# test_o1.net
KiCad netlist of a schematic drawn in EAGLE
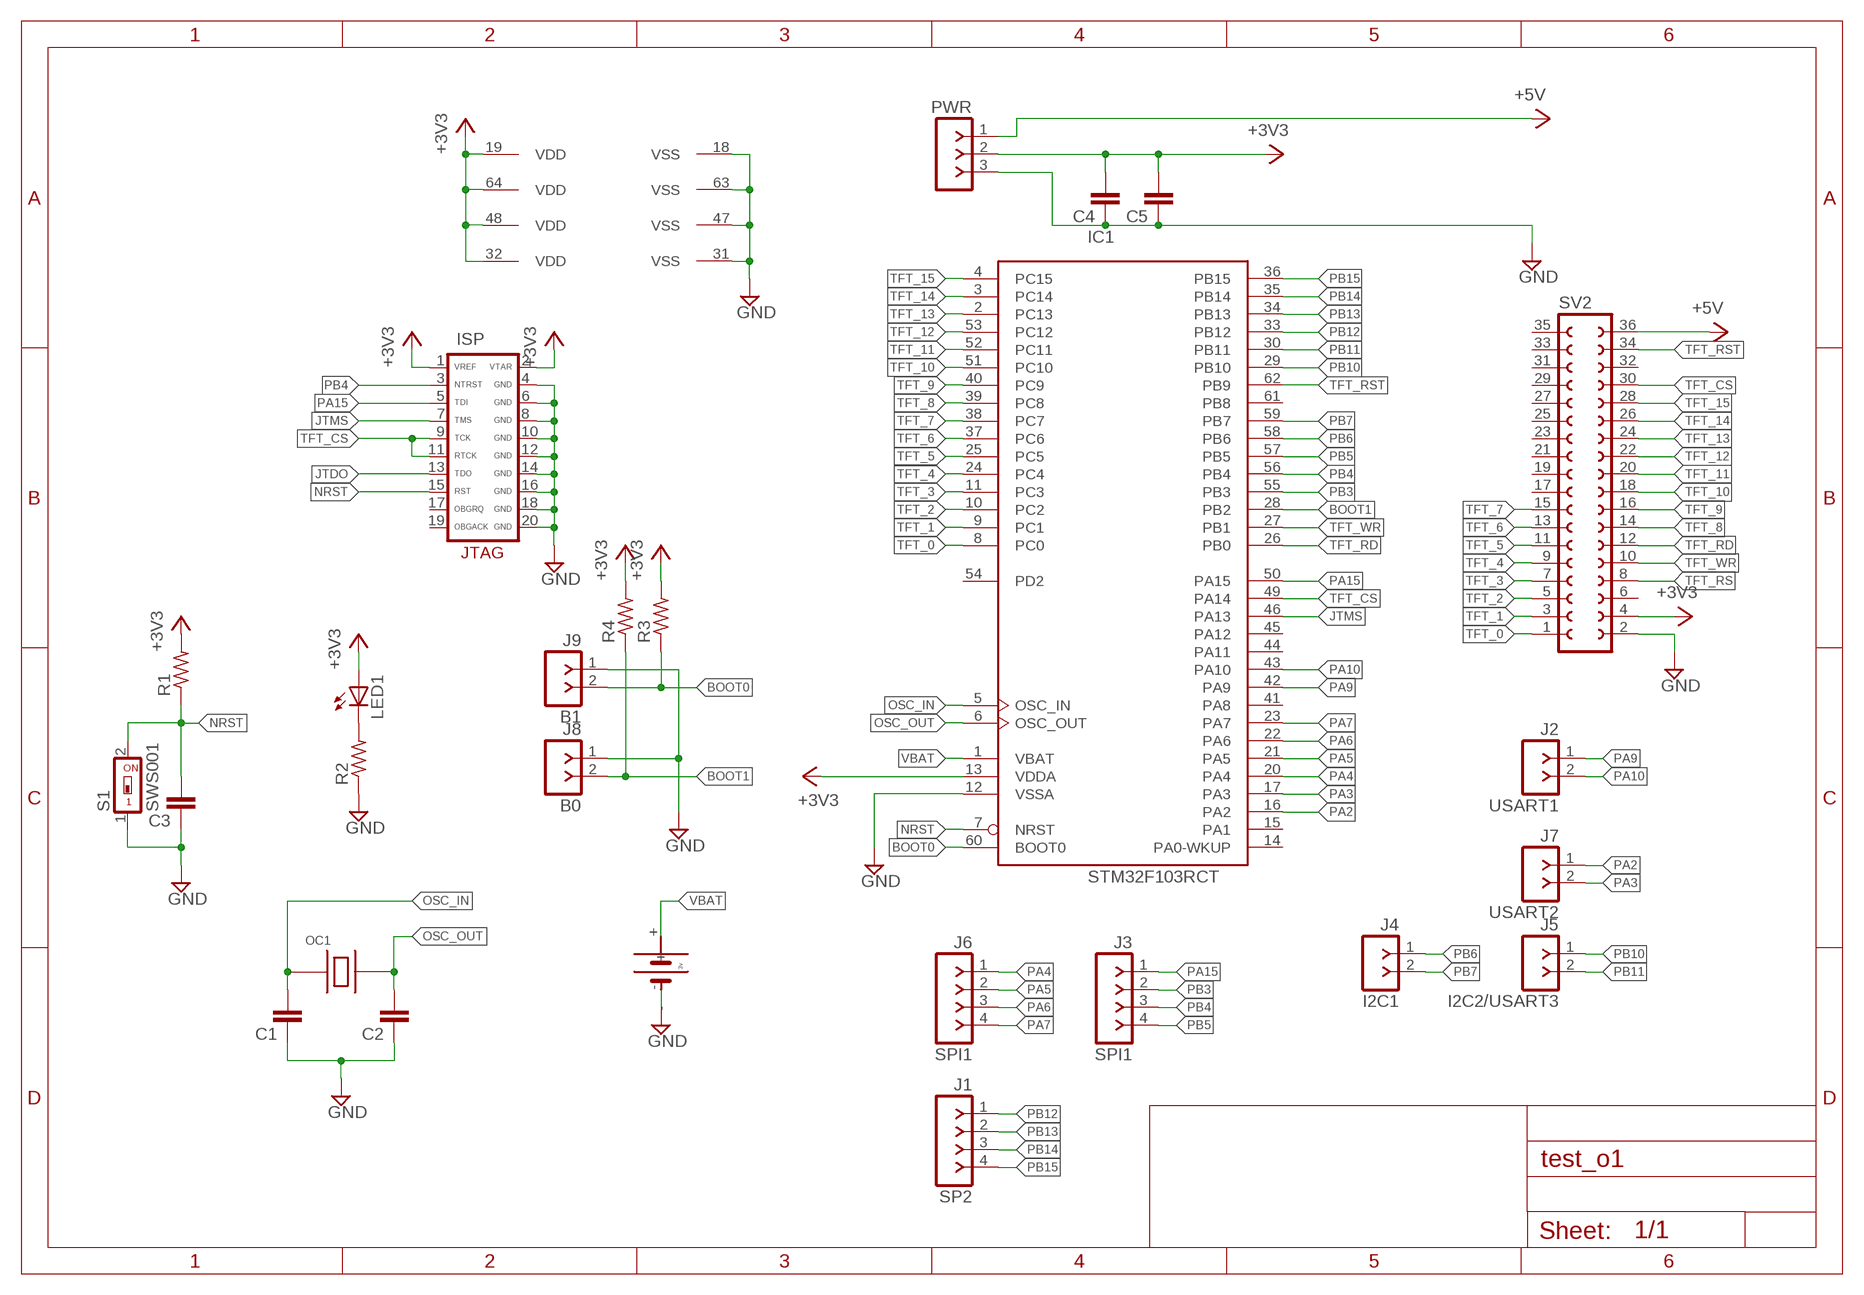
[diagram p0: schematic, sheet 1]

(export (version "E")
  (design (tool "Eeschema 10.0.6"))
  (components
    (comp (ref "C1")
      (value "C-EUC1206")
      (footprint "eagle-import:C1206")
      (libsource (lib "eagle-import") (part "C-EUC1206"))
    )
    (comp (ref "C2")
      (value "C-EUC1206")
      (footprint "eagle-import:C1206")
      (libsource (lib "eagle-import") (part "C-EUC1206"))
    )
    (comp (ref "C3")
      (value "C-EUC1206")
      (footprint "eagle-import:C1206")
      (libsource (lib "eagle-import") (part "C-EUC1206"))
    )
    (comp (ref "C4")
      (value "C-EUC1206")
      (footprint "eagle-import:C1206")
      (libsource (lib "eagle-import") (part "C-EUC1206"))
    )
    (comp (ref "C5")
      (value "C-EUC1206")
      (footprint "eagle-import:C1206")
      (libsource (lib "eagle-import") (part "C-EUC1206"))
    )
    (comp (ref "IC1")
      (value "STM32F103RCT")
      (footprint "eagle-import:LQFP64")
      (libsource (lib "eagle-import") (part "STM32F103RTC"))
    )
    (comp (ref "ISP")
      (value "JTAG")
      (footprint "eagle-import:PAK100_2500-20")
      (libsource (lib "eagle-import") (part "JTAG-ARM-PAK100/2500-20"))
    )
    (comp (ref "J1")
      (value "SP2")
      (footprint "eagle-import:SIP-100-04-40")
      (libsource (lib "eagle-import") (part "F-1X04-SIP-100-40"))
    )
    (comp (ref "J2")
      (value "USART1")
      (footprint "eagle-import:SIP-100-02-40")
      (libsource (lib "eagle-import") (part "F-1X02-SIP-100-40"))
    )
    (comp (ref "J3")
      (value "SPI1")
      (footprint "eagle-import:SIP-100-04-40")
      (libsource (lib "eagle-import") (part "F-1X04-SIP-100-40"))
    )
    (comp (ref "J4")
      (value "I2C1")
      (footprint "eagle-import:SIP-100-02-40")
      (libsource (lib "eagle-import") (part "F-1X02-SIP-100-40"))
    )
    (comp (ref "J5")
      (value "I2C2/USART3")
      (footprint "eagle-import:SIP-100-02-40")
      (libsource (lib "eagle-import") (part "F-1X02-SIP-100-40"))
    )
    (comp (ref "J6")
      (value "SPI1")
      (footprint "eagle-import:SIP-100-04-40")
      (libsource (lib "eagle-import") (part "F-1X04-SIP-100-40"))
    )
    (comp (ref "J7")
      (value "USART2")
      (footprint "eagle-import:SIP-100-02-40")
      (libsource (lib "eagle-import") (part "F-1X02-SIP-100-40"))
    )
    (comp (ref "J8")
      (value "B0")
      (footprint "eagle-import:SIP-100-02-40")
      (libsource (lib "eagle-import") (part "F-1X02-SIP-100-40"))
    )
    (comp (ref "J9")
      (value "B1")
      (footprint "eagle-import:SIP-100-02-40")
      (libsource (lib "eagle-import") (part "F-1X02-SIP-100-40"))
    )
    (comp (ref "LED1")
      (value "LEDSML1206")
      (footprint "eagle-import:SML1206")
      (libsource (lib "eagle-import") (part "LEDSML1206"))
    )
    (comp (ref "OC1")
      (value "SMAQ-7050B")
      (footprint "eagle-import:IQG7050B")
      (libsource (lib "eagle-import") (part "SMAQ-7050B"))
    )
    (comp (ref "PWR")
      (value "F-1X03-SIP-100-40")
      (footprint "eagle-import:SIP-100-03-40")
      (libsource (lib "eagle-import") (part "F-1X03-SIP-100-40"))
    )
    (comp (ref "R1")
      (value "R-US_R1206")
      (footprint "eagle-import:R1206")
      (libsource (lib "eagle-import") (part "R-US_R1206"))
    )
    (comp (ref "R2")
      (value "R-US_R1206")
      (footprint "eagle-import:R1206")
      (libsource (lib "eagle-import") (part "R-US_R1206"))
    )
    (comp (ref "R3")
      (value "R-US_R1206")
      (footprint "eagle-import:R1206")
      (libsource (lib "eagle-import") (part "R-US_R1206"))
    )
    (comp (ref "R4")
      (value "R-US_R1206")
      (footprint "eagle-import:R1206")
      (libsource (lib "eagle-import") (part "R-US_R1206"))
    )
    (comp (ref "S1")
      (value "SWS001")
      (footprint "eagle-import:SMS-001")
      (libsource (lib "eagle-import") (part "SWS001"))
    )
    (comp (ref "SV2")
      (value "FE18-2")
      (footprint "eagle-import:FE18-2")
      (libsource (lib "eagle-import") (part "FE18-2"))
    )
    (comp (ref "U$2")
      (value "1220BATTERY_SF")
      (footprint "eagle-import:1220BATTERY")
      (libsource (lib "eagle-import") (part "1220BATTERY_SF"))
    )
  )
  (nets
    (net (code "1") (name "+3V3") (class "Default")
      (node (ref "C4") (pin "2") (pinfunction "2_2") (pintype "passive"))
      (node (ref "C5") (pin "2") (pinfunction "2_2") (pintype "passive"))
      (node (ref "IC1") (pin "13") (pinfunction "VDDA_13") (pintype "power_in"))
      (node (ref "IC1") (pin "19") (pinfunction "VDD_19") (pintype "power_in"))
      (node (ref "IC1") (pin "32") (pinfunction "VDD_32") (pintype "power_in"))
      (node (ref "IC1") (pin "48") (pinfunction "VDD_48") (pintype "power_in"))
      (node (ref "IC1") (pin "64") (pinfunction "VDD_64") (pintype "power_in"))
      (node (ref "ISP") (pin "1") (pinfunction "VREF_1") (pintype "passive"))
      (node (ref "ISP") (pin "2") (pinfunction "VTAR_2") (pintype "passive"))
      (node (ref "LED1") (pin "A") (pinfunction "A_A") (pintype "passive"))
      (node (ref "PWR") (pin "2") (pinfunction "2_2") (pintype "passive"))
      (node (ref "R1") (pin "2") (pinfunction "2_2") (pintype "passive"))
      (node (ref "R3") (pin "2") (pinfunction "2_2") (pintype "passive"))
      (node (ref "R4") (pin "2") (pinfunction "2_2") (pintype "passive"))
      (node (ref "SV2") (pin "4") (pinfunction "4_4") (pintype "passive"))
    )
    (net (code "2") (name "+5V") (class "Default")
      (node (ref "PWR") (pin "1") (pinfunction "1_1") (pintype "passive"))
      (node (ref "SV2") (pin "36") (pinfunction "36_36") (pintype "passive"))
    )
    (net (code "3") (name "BOOT0") (class "Default")
      (node (ref "IC1") (pin "60") (pinfunction "BOOT0_60") (pintype "input"))
      (node (ref "J9") (pin "2") (pinfunction "2_2") (pintype "passive"))
      (node (ref "R3") (pin "1") (pinfunction "1_1") (pintype "passive"))
    )
    (net (code "4") (name "BOOT1") (class "Default")
      (node (ref "IC1") (pin "28") (pinfunction "PB2_28") (pintype "bidirectional"))
      (node (ref "J8") (pin "2") (pinfunction "2_2") (pintype "passive"))
      (node (ref "R4") (pin "1") (pinfunction "1_1") (pintype "passive"))
    )
    (net (code "5") (name "GND") (class "Default")
      (node (ref "C1") (pin "1") (pinfunction "1_1") (pintype "passive"))
      (node (ref "C2") (pin "1") (pinfunction "1_1") (pintype "passive"))
      (node (ref "C3") (pin "1") (pinfunction "1_1") (pintype "passive"))
      (node (ref "C4") (pin "1") (pinfunction "1_1") (pintype "passive"))
      (node (ref "C5") (pin "1") (pinfunction "1_1") (pintype "passive"))
      (node (ref "IC1") (pin "12") (pinfunction "VSSA_12") (pintype "power_in"))
      (node (ref "IC1") (pin "18") (pinfunction "VSS_18") (pintype "power_in"))
      (node (ref "IC1") (pin "31") (pinfunction "VSS_31") (pintype "power_in"))
      (node (ref "IC1") (pin "47") (pinfunction "VSS_47") (pintype "power_in"))
      (node (ref "IC1") (pin "63") (pinfunction "VSS_63") (pintype "power_in"))
      (node (ref "ISP") (pin "10") (pinfunction "GND_10") (pintype "passive"))
      (node (ref "ISP") (pin "12") (pinfunction "GND_12") (pintype "passive"))
      (node (ref "ISP") (pin "14") (pinfunction "GND_14") (pintype "passive"))
      (node (ref "ISP") (pin "16") (pinfunction "GND_16") (pintype "passive"))
      (node (ref "ISP") (pin "18") (pinfunction "GND_18") (pintype "passive"))
      (node (ref "ISP") (pin "20") (pinfunction "GND_20") (pintype "passive"))
      (node (ref "ISP") (pin "4") (pinfunction "GND_4") (pintype "passive"))
      (node (ref "ISP") (pin "6") (pinfunction "GND_6") (pintype "passive"))
      (node (ref "ISP") (pin "8") (pinfunction "GND_8") (pintype "passive"))
      (node (ref "J8") (pin "1") (pinfunction "1_1") (pintype "passive"))
      (node (ref "J9") (pin "1") (pinfunction "1_1") (pintype "passive"))
      (node (ref "PWR") (pin "3") (pinfunction "3_3") (pintype "passive"))
      (node (ref "R2") (pin "1") (pinfunction "1_1") (pintype "passive"))
      (node (ref "S1") (pin "1") (pinfunction "1_1") (pintype "passive"))
      (node (ref "SV2") (pin "2") (pinfunction "2_2") (pintype "passive"))
      (node (ref "U$2") (pin "-") (pinfunction "-_-") (pintype "bidirectional"))
    )
    (net (code "6") (name "JTDO") (class "Default")
      (node (ref "ISP") (pin "13") (pinfunction "TDO_13") (pintype "passive"))
    )
    (net (code "7") (name "JTMS") (class "Default")
      (node (ref "IC1") (pin "46") (pinfunction "PA13_46") (pintype "bidirectional"))
      (node (ref "ISP") (pin "7") (pinfunction "TMS_7") (pintype "passive"))
    )
    (net (code "8") (name "NRST") (class "Default")
      (node (ref "C3") (pin "2") (pinfunction "2_2") (pintype "passive"))
      (node (ref "IC1") (pin "7") (pinfunction "NRST_7") (pintype "bidirectional"))
      (node (ref "ISP") (pin "15") (pinfunction "RST_15") (pintype "passive"))
      (node (ref "R1") (pin "1") (pinfunction "1_1") (pintype "passive"))
      (node (ref "S1") (pin "2") (pinfunction "2_2") (pintype "passive"))
    )
    (net (code "9") (name "Net-(LED1-PadC)") (class "Default")
      (node (ref "LED1") (pin "C") (pinfunction "C_C") (pintype "passive"))
      (node (ref "R2") (pin "2") (pinfunction "2_2") (pintype "passive"))
    )
    (net (code "10") (name "OSC_IN") (class "Default")
      (node (ref "C1") (pin "2") (pinfunction "2_2") (pintype "passive"))
      (node (ref "IC1") (pin "5") (pinfunction "OSC_IN_5") (pintype "bidirectional"))
      (node (ref "OC1") (pin "P$1") (pinfunction "PIN1_P$1") (pintype "bidirectional"))
    )
    (net (code "11") (name "OSC_OUT") (class "Default")
      (node (ref "C2") (pin "2") (pinfunction "2_2") (pintype "passive"))
      (node (ref "IC1") (pin "6") (pinfunction "OSC_OUT_6") (pintype "bidirectional"))
      (node (ref "OC1") (pin "P$3") (pinfunction "PIN2_P$3") (pintype "bidirectional"))
    )
    (net (code "12") (name "PA2") (class "Default")
      (node (ref "IC1") (pin "16") (pinfunction "PA2_16") (pintype "bidirectional"))
      (node (ref "J7") (pin "1") (pinfunction "1_1") (pintype "passive"))
    )
    (net (code "13") (name "PA3") (class "Default")
      (node (ref "IC1") (pin "17") (pinfunction "PA3_17") (pintype "bidirectional"))
      (node (ref "J7") (pin "2") (pinfunction "2_2") (pintype "passive"))
    )
    (net (code "14") (name "PA4") (class "Default")
      (node (ref "IC1") (pin "20") (pinfunction "PA4_20") (pintype "bidirectional"))
      (node (ref "J6") (pin "1") (pinfunction "1_1") (pintype "passive"))
    )
    (net (code "15") (name "PA5") (class "Default")
      (node (ref "IC1") (pin "21") (pinfunction "PA5_21") (pintype "bidirectional"))
      (node (ref "J6") (pin "2") (pinfunction "2_2") (pintype "passive"))
    )
    (net (code "16") (name "PA6") (class "Default")
      (node (ref "IC1") (pin "22") (pinfunction "PA6_22") (pintype "bidirectional"))
      (node (ref "J6") (pin "3") (pinfunction "3_3") (pintype "passive"))
    )
    (net (code "17") (name "PA7") (class "Default")
      (node (ref "IC1") (pin "23") (pinfunction "PA7_23") (pintype "bidirectional"))
      (node (ref "J6") (pin "4") (pinfunction "4_4") (pintype "passive"))
    )
    (net (code "18") (name "PA9") (class "Default")
      (node (ref "IC1") (pin "42") (pinfunction "PA9_42") (pintype "bidirectional"))
      (node (ref "J2") (pin "1") (pinfunction "1_1") (pintype "passive"))
    )
    (net (code "19") (name "PA10") (class "Default")
      (node (ref "IC1") (pin "43") (pinfunction "PA10_43") (pintype "bidirectional"))
      (node (ref "J2") (pin "2") (pinfunction "2_2") (pintype "passive"))
    )
    (net (code "20") (name "PA15") (class "Default")
      (node (ref "IC1") (pin "50") (pinfunction "PA15_50") (pintype "bidirectional"))
      (node (ref "ISP") (pin "5") (pinfunction "TDI_5") (pintype "passive"))
      (node (ref "J3") (pin "1") (pinfunction "1_1") (pintype "passive"))
    )
    (net (code "21") (name "PB3") (class "Default")
      (node (ref "IC1") (pin "55") (pinfunction "PB3_55") (pintype "bidirectional"))
      (node (ref "J3") (pin "2") (pinfunction "2_2") (pintype "passive"))
    )
    (net (code "22") (name "PB4") (class "Default")
      (node (ref "IC1") (pin "56") (pinfunction "PB4_56") (pintype "bidirectional"))
      (node (ref "ISP") (pin "3") (pinfunction "NTRST_3") (pintype "passive"))
      (node (ref "J3") (pin "3") (pinfunction "3_3") (pintype "passive"))
    )
    (net (code "23") (name "PB5") (class "Default")
      (node (ref "IC1") (pin "57") (pinfunction "PB5_57") (pintype "bidirectional"))
      (node (ref "J3") (pin "4") (pinfunction "4_4") (pintype "passive"))
    )
    (net (code "24") (name "PB6") (class "Default")
      (node (ref "IC1") (pin "58") (pinfunction "PB6_58") (pintype "bidirectional"))
      (node (ref "J4") (pin "1") (pinfunction "1_1") (pintype "passive"))
    )
    (net (code "25") (name "PB7") (class "Default")
      (node (ref "IC1") (pin "59") (pinfunction "PB7_59") (pintype "bidirectional"))
      (node (ref "J4") (pin "2") (pinfunction "2_2") (pintype "passive"))
    )
    (net (code "26") (name "PB10") (class "Default")
      (node (ref "IC1") (pin "29") (pinfunction "PB10_29") (pintype "bidirectional"))
      (node (ref "J5") (pin "1") (pinfunction "1_1") (pintype "passive"))
    )
    (net (code "27") (name "PB11") (class "Default")
      (node (ref "IC1") (pin "30") (pinfunction "PB11_30") (pintype "bidirectional"))
      (node (ref "J5") (pin "2") (pinfunction "2_2") (pintype "passive"))
    )
    (net (code "28") (name "PB12") (class "Default")
      (node (ref "IC1") (pin "33") (pinfunction "PB12_33") (pintype "bidirectional"))
      (node (ref "J1") (pin "1") (pinfunction "1_1") (pintype "passive"))
    )
    (net (code "29") (name "PB13") (class "Default")
      (node (ref "IC1") (pin "34") (pinfunction "PB13_34") (pintype "bidirectional"))
      (node (ref "J1") (pin "2") (pinfunction "2_2") (pintype "passive"))
    )
    (net (code "30") (name "PB14") (class "Default")
      (node (ref "IC1") (pin "35") (pinfunction "PB14_35") (pintype "bidirectional"))
      (node (ref "J1") (pin "3") (pinfunction "3_3") (pintype "passive"))
    )
    (net (code "31") (name "PB15") (class "Default")
      (node (ref "IC1") (pin "36") (pinfunction "PB15_36") (pintype "bidirectional"))
      (node (ref "J1") (pin "4") (pinfunction "4_4") (pintype "passive"))
    )
    (net (code "32") (name "TFT_0") (class "Default")
      (node (ref "IC1") (pin "8") (pinfunction "PC0_8") (pintype "bidirectional"))
      (node (ref "SV2") (pin "1") (pinfunction "1_1") (pintype "passive"))
    )
    (net (code "33") (name "TFT_1") (class "Default")
      (node (ref "IC1") (pin "9") (pinfunction "PC1_9") (pintype "bidirectional"))
      (node (ref "SV2") (pin "3") (pinfunction "3_3") (pintype "passive"))
    )
    (net (code "34") (name "TFT_2") (class "Default")
      (node (ref "IC1") (pin "10") (pinfunction "PC2_10") (pintype "bidirectional"))
      (node (ref "SV2") (pin "5") (pinfunction "5_5") (pintype "passive"))
    )
    (net (code "35") (name "TFT_3") (class "Default")
      (node (ref "IC1") (pin "11") (pinfunction "PC3_11") (pintype "bidirectional"))
      (node (ref "SV2") (pin "7") (pinfunction "7_7") (pintype "passive"))
    )
    (net (code "36") (name "TFT_4") (class "Default")
      (node (ref "IC1") (pin "24") (pinfunction "PC4_24") (pintype "bidirectional"))
      (node (ref "SV2") (pin "9") (pinfunction "9_9") (pintype "passive"))
    )
    (net (code "37") (name "TFT_5") (class "Default")
      (node (ref "IC1") (pin "25") (pinfunction "PC5_25") (pintype "bidirectional"))
      (node (ref "SV2") (pin "11") (pinfunction "11_11") (pintype "passive"))
    )
    (net (code "38") (name "TFT_6") (class "Default")
      (node (ref "IC1") (pin "37") (pinfunction "PC6_37") (pintype "bidirectional"))
      (node (ref "SV2") (pin "13") (pinfunction "13_13") (pintype "passive"))
    )
    (net (code "39") (name "TFT_7") (class "Default")
      (node (ref "IC1") (pin "38") (pinfunction "PC7_38") (pintype "bidirectional"))
      (node (ref "SV2") (pin "15") (pinfunction "15_15") (pintype "passive"))
    )
    (net (code "40") (name "TFT_8") (class "Default")
      (node (ref "IC1") (pin "39") (pinfunction "PC8_39") (pintype "bidirectional"))
      (node (ref "SV2") (pin "14") (pinfunction "14_14") (pintype "passive"))
    )
    (net (code "41") (name "TFT_9") (class "Default")
      (node (ref "IC1") (pin "40") (pinfunction "PC9_40") (pintype "bidirectional"))
      (node (ref "SV2") (pin "16") (pinfunction "16_16") (pintype "passive"))
    )
    (net (code "42") (name "TFT_10") (class "Default")
      (node (ref "IC1") (pin "51") (pinfunction "PC10_51") (pintype "bidirectional"))
      (node (ref "SV2") (pin "18") (pinfunction "18_18") (pintype "passive"))
    )
    (net (code "43") (name "TFT_11") (class "Default")
      (node (ref "IC1") (pin "52") (pinfunction "PC11_52") (pintype "bidirectional"))
      (node (ref "SV2") (pin "20") (pinfunction "20_20") (pintype "passive"))
    )
    (net (code "44") (name "TFT_12") (class "Default")
      (node (ref "IC1") (pin "53") (pinfunction "PC12_53") (pintype "bidirectional"))
      (node (ref "SV2") (pin "22") (pinfunction "22_22") (pintype "passive"))
    )
    (net (code "45") (name "TFT_13") (class "Default")
      (node (ref "IC1") (pin "2") (pinfunction "PC13_2") (pintype "bidirectional"))
      (node (ref "SV2") (pin "24") (pinfunction "24_24") (pintype "passive"))
    )
    (net (code "46") (name "TFT_14") (class "Default")
      (node (ref "IC1") (pin "3") (pinfunction "PC14_3") (pintype "bidirectional"))
      (node (ref "SV2") (pin "26") (pinfunction "26_26") (pintype "passive"))
    )
    (net (code "47") (name "TFT_15") (class "Default")
      (node (ref "IC1") (pin "4") (pinfunction "PC15_4") (pintype "bidirectional"))
      (node (ref "SV2") (pin "28") (pinfunction "28_28") (pintype "passive"))
    )
    (net (code "48") (name "TFT_CS") (class "Default")
      (node (ref "IC1") (pin "49") (pinfunction "PA14_49") (pintype "bidirectional"))
      (node (ref "ISP") (pin "11") (pinfunction "RTCK_11") (pintype "passive"))
      (node (ref "ISP") (pin "9") (pinfunction "TCK_9") (pintype "passive"))
      (node (ref "SV2") (pin "30") (pinfunction "30_30") (pintype "passive"))
    )
    (net (code "49") (name "TFT_RD") (class "Default")
      (node (ref "IC1") (pin "26") (pinfunction "PB0_26") (pintype "bidirectional"))
      (node (ref "SV2") (pin "12") (pinfunction "12_12") (pintype "passive"))
    )
    (net (code "50") (name "TFT_RS") (class "Default")
      (node (ref "SV2") (pin "8") (pinfunction "8_8") (pintype "passive"))
    )
    (net (code "51") (name "TFT_RST") (class "Default")
      (node (ref "IC1") (pin "62") (pinfunction "PB9_62") (pintype "bidirectional"))
      (node (ref "SV2") (pin "34") (pinfunction "34_34") (pintype "passive"))
    )
    (net (code "52") (name "TFT_WR") (class "Default")
      (node (ref "IC1") (pin "27") (pinfunction "PB1_27") (pintype "bidirectional"))
      (node (ref "SV2") (pin "10") (pinfunction "10_10") (pintype "passive"))
    )
    (net (code "53") (name "VBAT") (class "Default")
      (node (ref "IC1") (pin "1") (pinfunction "VBAT_1") (pintype "power_in"))
      (node (ref "U$2") (pin "+") (pinfunction "+_+") (pintype "bidirectional"))
    )
    (net (code "54") (name "unconnected-(IC1A-PA0-WKUP-Pad14)") (class "Default")
      (node (ref "IC1") (pin "14") (pinfunction "PA0-WKUP_14") (pintype "bidirectional"))
    )
    (net (code "55") (name "unconnected-(IC1A-PA1-Pad15)") (class "Default")
      (node (ref "IC1") (pin "15") (pinfunction "PA1_15") (pintype "bidirectional"))
    )
    (net (code "56") (name "unconnected-(IC1A-PA8-Pad41)") (class "Default")
      (node (ref "IC1") (pin "41") (pinfunction "PA8_41") (pintype "bidirectional"))
    )
    (net (code "57") (name "unconnected-(IC1A-PA11-Pad44)") (class "Default")
      (node (ref "IC1") (pin "44") (pinfunction "PA11_44") (pintype "bidirectional"))
    )
    (net (code "58") (name "unconnected-(IC1A-PA12-Pad45)") (class "Default")
      (node (ref "IC1") (pin "45") (pinfunction "PA12_45") (pintype "bidirectional"))
    )
    (net (code "59") (name "unconnected-(IC1A-PB8-Pad61)") (class "Default")
      (node (ref "IC1") (pin "61") (pinfunction "PB8_61") (pintype "bidirectional"))
    )
    (net (code "60") (name "unconnected-(IC1A-PD2-Pad54)") (class "Default")
      (node (ref "IC1") (pin "54") (pinfunction "PD2_54") (pintype "bidirectional"))
    )
    (net (code "61") (name "unconnected-(ISP-OBGACK-Pad19)") (class "Default")
      (node (ref "ISP") (pin "19") (pinfunction "OBGACK_19") (pintype "passive"))
    )
    (net (code "62") (name "unconnected-(ISP-OBGRQ-Pad17)") (class "Default")
      (node (ref "ISP") (pin "17") (pinfunction "OBGRQ_17") (pintype "passive"))
    )
    (net (code "63") (name "unconnected-(SV2-Pad6)") (class "Default")
      (node (ref "SV2") (pin "6") (pinfunction "6_6") (pintype "passive"))
    )
    (net (code "64") (name "unconnected-(SV2-Pad17)") (class "Default")
      (node (ref "SV2") (pin "17") (pinfunction "17_17") (pintype "passive"))
    )
    (net (code "65") (name "unconnected-(SV2-Pad19)") (class "Default")
      (node (ref "SV2") (pin "19") (pinfunction "19_19") (pintype "passive"))
    )
    (net (code "66") (name "unconnected-(SV2-Pad21)") (class "Default")
      (node (ref "SV2") (pin "21") (pinfunction "21_21") (pintype "passive"))
    )
    (net (code "67") (name "unconnected-(SV2-Pad23)") (class "Default")
      (node (ref "SV2") (pin "23") (pinfunction "23_23") (pintype "passive"))
    )
    (net (code "68") (name "unconnected-(SV2-Pad25)") (class "Default")
      (node (ref "SV2") (pin "25") (pinfunction "25_25") (pintype "passive"))
    )
    (net (code "69") (name "unconnected-(SV2-Pad27)") (class "Default")
      (node (ref "SV2") (pin "27") (pinfunction "27_27") (pintype "passive"))
    )
    (net (code "70") (name "unconnected-(SV2-Pad29)") (class "Default")
      (node (ref "SV2") (pin "29") (pinfunction "29_29") (pintype "passive"))
    )
    (net (code "71") (name "unconnected-(SV2-Pad31)") (class "Default")
      (node (ref "SV2") (pin "31") (pinfunction "31_31") (pintype "passive"))
    )
    (net (code "72") (name "unconnected-(SV2-Pad32)") (class "Default")
      (node (ref "SV2") (pin "32") (pinfunction "32_32") (pintype "passive"))
    )
    (net (code "73") (name "unconnected-(SV2-Pad33)") (class "Default")
      (node (ref "SV2") (pin "33") (pinfunction "33_33") (pintype "passive"))
    )
    (net (code "74") (name "unconnected-(SV2-Pad35)") (class "Default")
      (node (ref "SV2") (pin "35") (pinfunction "35_35") (pintype "passive"))
    )
  )
)
